# NixiTubeClock.net
KiCad netlist of a schematic drawn in EAGLE
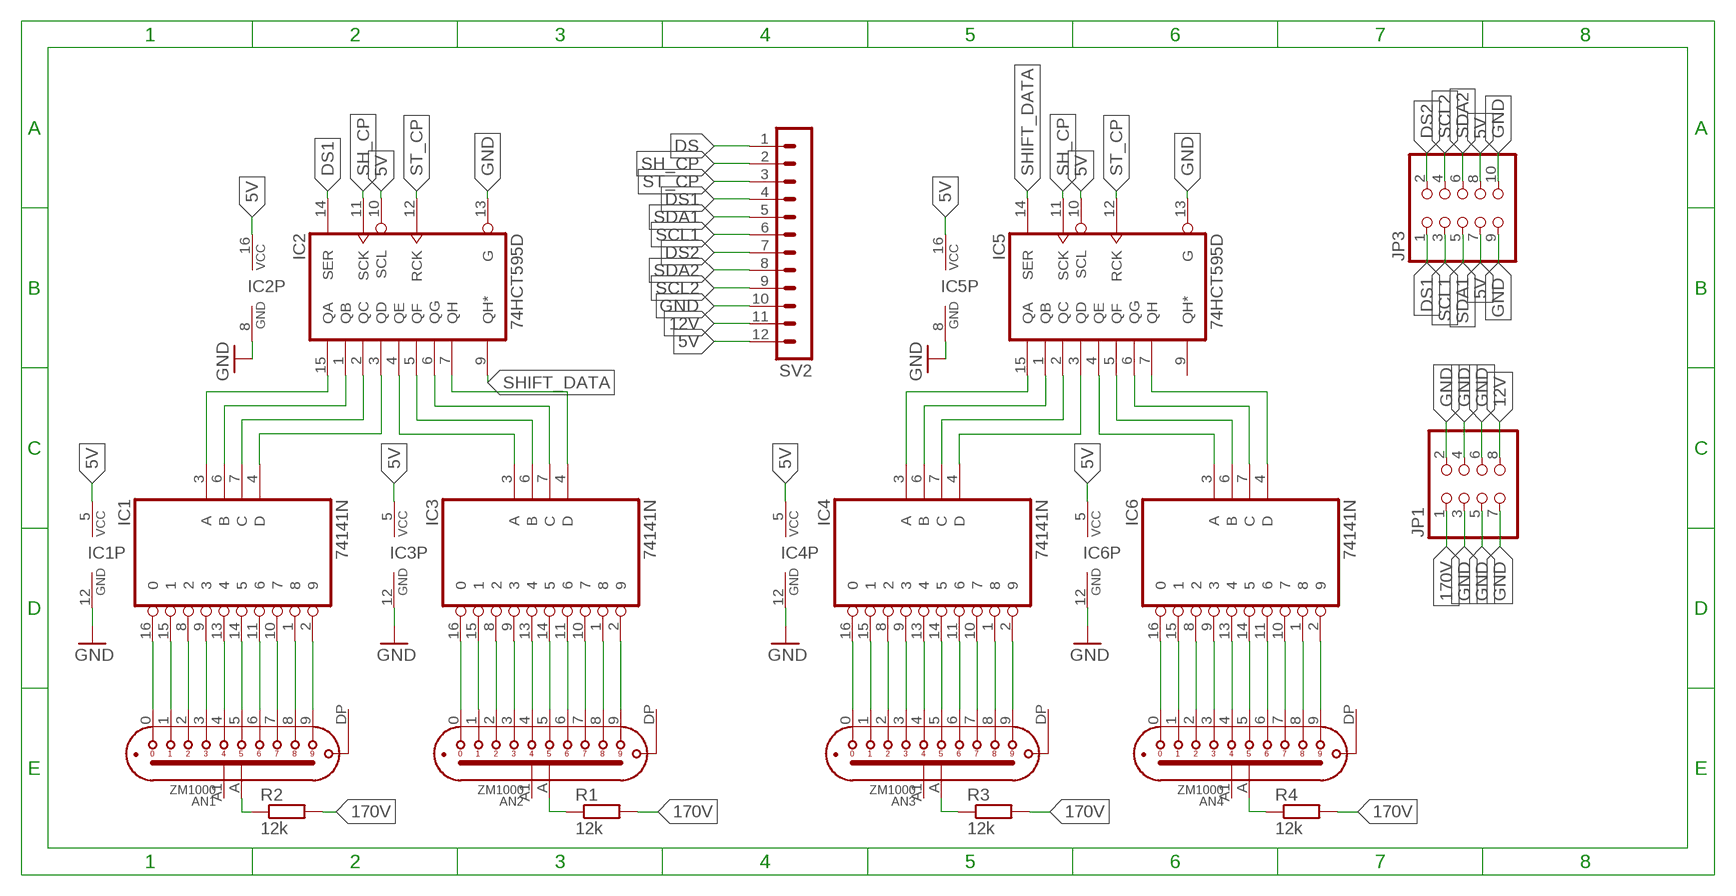
[diagram p0: schematic, sheet 1]
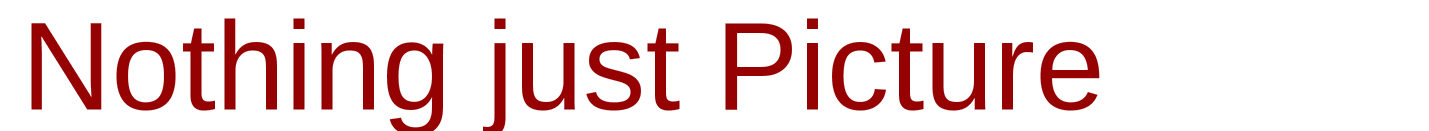
[diagram p1: schematic, sheet 2]

(export (version "E")
  (design (tool "Eeschema 10.0.6"))
  (components
    (comp (ref "AN1")
      (value "ZM1000")
      (footprint "eagle-import:ZM1000")
      (libsource (lib "eagle-import") (part "ZM1000"))
    )
    (comp (ref "AN2")
      (value "ZM1000")
      (footprint "eagle-import:ZM1000")
      (libsource (lib "eagle-import") (part "ZM1000"))
    )
    (comp (ref "AN3")
      (value "ZM1000")
      (footprint "eagle-import:ZM1000")
      (libsource (lib "eagle-import") (part "ZM1000"))
    )
    (comp (ref "AN4")
      (value "ZM1000")
      (footprint "eagle-import:ZM1000")
      (libsource (lib "eagle-import") (part "ZM1000"))
    )
    (comp (ref "IC1")
      (value "74141N")
      (footprint "eagle-import:DIL16")
      (libsource (lib "eagle-import") (part "74141N"))
    )
    (comp (ref "IC2")
      (value "74HCT595D")
      (footprint "eagle-import:SO16")
      (libsource (lib "eagle-import") (part "74595DHCT"))
    )
    (comp (ref "IC3")
      (value "74141N")
      (footprint "eagle-import:DIL16")
      (libsource (lib "eagle-import") (part "74141N"))
    )
    (comp (ref "IC4")
      (value "74141N")
      (footprint "eagle-import:DIL16")
      (libsource (lib "eagle-import") (part "74141N"))
    )
    (comp (ref "IC5")
      (value "74HCT595D")
      (footprint "eagle-import:SO16")
      (libsource (lib "eagle-import") (part "74595DHCT"))
    )
    (comp (ref "IC6")
      (value "74141N")
      (footprint "eagle-import:DIL16")
      (libsource (lib "eagle-import") (part "74141N"))
    )
    (comp (ref "JP1")
      (value "PINHD-2X4/90")
      (footprint "eagle-import:2X04_90")
      (libsource (lib "eagle-import") (part "PINHD-2X4/90"))
    )
    (comp (ref "JP3")
      (value "PINHD-2X5/90")
      (footprint "eagle-import:2X05_90")
      (libsource (lib "eagle-import") (part "PINHD-2X5/90"))
    )
    (comp (ref "R1")
      (value "12k")
      (footprint "eagle-import:R1206")
      (libsource (lib "eagle-import") (part "R-EU_1206R1206"))
    )
    (comp (ref "R2")
      (value "12k")
      (footprint "eagle-import:R1206")
      (libsource (lib "eagle-import") (part "R-EU_1206R1206"))
    )
    (comp (ref "R3")
      (value "12k")
      (footprint "eagle-import:R1206")
      (libsource (lib "eagle-import") (part "R-EU_1206R1206"))
    )
    (comp (ref "R4")
      (value "12k")
      (footprint "eagle-import:R1206")
      (libsource (lib "eagle-import") (part "R-EU_1206R1206"))
    )
    (comp (ref "SV2")
      (value "MA12-1")
      (footprint "eagle-import:MA12-1")
      (libsource (lib "eagle-import") (part "MA12-1"))
    )
  )
  (nets
    (net (code "1") (name "5V") (class "Default")
      (node (ref "IC1") (pin "5") (pinfunction "VCC_5") (pintype "power_in"))
      (node (ref "IC2") (pin "10") (pinfunction "SCL_10") (pintype "input"))
      (node (ref "IC2") (pin "16") (pinfunction "VCC_16") (pintype "power_in"))
      (node (ref "IC3") (pin "5") (pinfunction "VCC_5") (pintype "power_in"))
      (node (ref "IC4") (pin "5") (pinfunction "VCC_5") (pintype "power_in"))
      (node (ref "IC5") (pin "10") (pinfunction "SCL_10") (pintype "input"))
      (node (ref "IC5") (pin "16") (pinfunction "VCC_16") (pintype "power_in"))
      (node (ref "IC6") (pin "5") (pinfunction "VCC_5") (pintype "power_in"))
      (node (ref "JP3") (pin "7") (pinfunction "7_7") (pintype "passive"))
      (node (ref "JP3") (pin "8") (pinfunction "8_8") (pintype "passive"))
      (node (ref "SV2") (pin "12") (pinfunction "12_12") (pintype "passive"))
    )
    (net (code "2") (name "12V") (class "Default")
      (node (ref "JP1") (pin "8") (pinfunction "8_8") (pintype "passive"))
      (node (ref "SV2") (pin "11") (pinfunction "11_11") (pintype "passive"))
    )
    (net (code "3") (name "170V") (class "Default")
      (node (ref "JP1") (pin "1") (pinfunction "1_1") (pintype "passive"))
      (node (ref "R1") (pin "2") (pinfunction "2_2") (pintype "passive"))
      (node (ref "R2") (pin "2") (pinfunction "2_2") (pintype "passive"))
      (node (ref "R3") (pin "2") (pinfunction "2_2") (pintype "passive"))
      (node (ref "R4") (pin "2") (pinfunction "2_2") (pintype "passive"))
    )
    (net (code "4") (name "DS") (class "Default")
      (node (ref "SV2") (pin "1") (pinfunction "1_1") (pintype "passive"))
    )
    (net (code "5") (name "DS1") (class "Default")
      (node (ref "IC2") (pin "14") (pinfunction "SER_14") (pintype "input"))
      (node (ref "JP3") (pin "1") (pinfunction "1_1") (pintype "passive"))
      (node (ref "SV2") (pin "4") (pinfunction "4_4") (pintype "passive"))
    )
    (net (code "6") (name "DS2") (class "Default")
      (node (ref "JP3") (pin "2") (pinfunction "2_2") (pintype "passive"))
      (node (ref "SV2") (pin "7") (pinfunction "7_7") (pintype "passive"))
    )
    (net (code "7") (name "GND") (class "Default")
      (node (ref "IC1") (pin "12") (pinfunction "GND_12") (pintype "power_in"))
      (node (ref "IC2") (pin "13") (pinfunction "G_13") (pintype "input"))
      (node (ref "IC2") (pin "8") (pinfunction "GND_8") (pintype "power_in"))
      (node (ref "IC3") (pin "12") (pinfunction "GND_12") (pintype "power_in"))
      (node (ref "IC4") (pin "12") (pinfunction "GND_12") (pintype "power_in"))
      (node (ref "IC5") (pin "13") (pinfunction "G_13") (pintype "input"))
      (node (ref "IC5") (pin "8") (pinfunction "GND_8") (pintype "power_in"))
      (node (ref "IC6") (pin "12") (pinfunction "GND_12") (pintype "power_in"))
      (node (ref "JP1") (pin "2") (pinfunction "2_2") (pintype "passive"))
      (node (ref "JP1") (pin "3") (pinfunction "3_3") (pintype "passive"))
      (node (ref "JP1") (pin "4") (pinfunction "4_4") (pintype "passive"))
      (node (ref "JP1") (pin "5") (pinfunction "5_5") (pintype "passive"))
      (node (ref "JP1") (pin "6") (pinfunction "6_6") (pintype "passive"))
      (node (ref "JP1") (pin "7") (pinfunction "7_7") (pintype "passive"))
      (node (ref "JP3") (pin "10") (pinfunction "10_10") (pintype "passive"))
      (node (ref "JP3") (pin "9") (pinfunction "9_9") (pintype "passive"))
      (node (ref "SV2") (pin "10") (pinfunction "10_10") (pintype "passive"))
    )
    (net (code "8") (name "Net-(AN1-A1)") (class "Default")
      (node (ref "AN1") (pin "A") (pinfunction "A1_A") (pintype "passive"))
      (node (ref "R2") (pin "1") (pinfunction "1_1") (pintype "passive"))
    )
    (net (code "9") (name "Net-(AN2-A1)") (class "Default")
      (node (ref "AN2") (pin "A") (pinfunction "A1_A") (pintype "passive"))
      (node (ref "R1") (pin "1") (pinfunction "1_1") (pintype "passive"))
    )
    (net (code "10") (name "Net-(AN3-A1)") (class "Default")
      (node (ref "AN3") (pin "A") (pinfunction "A1_A") (pintype "passive"))
      (node (ref "R3") (pin "1") (pinfunction "1_1") (pintype "passive"))
    )
    (net (code "11") (name "Net-(AN4-A1)") (class "Default")
      (node (ref "AN4") (pin "A") (pinfunction "A1_A") (pintype "passive"))
      (node (ref "R4") (pin "1") (pinfunction "1_1") (pintype "passive"))
    )
    (net (code "12") (name "Net-(IC1A-0)") (class "Default")
      (node (ref "AN1") (pin "0") (pinfunction "0_0") (pintype "passive"))
      (node (ref "IC1") (pin "16") (pinfunction "0_16") (pintype "open_collector"))
    )
    (net (code "13") (name "Net-(IC1A-1)") (class "Default")
      (node (ref "AN1") (pin "1") (pinfunction "1_1") (pintype "passive"))
      (node (ref "IC1") (pin "15") (pinfunction "1_15") (pintype "open_collector"))
    )
    (net (code "14") (name "Net-(IC1A-2)") (class "Default")
      (node (ref "AN1") (pin "2") (pinfunction "2_2") (pintype "passive"))
      (node (ref "IC1") (pin "8") (pinfunction "2_8") (pintype "open_collector"))
    )
    (net (code "15") (name "Net-(IC1A-3)") (class "Default")
      (node (ref "AN1") (pin "3") (pinfunction "3_3") (pintype "passive"))
      (node (ref "IC1") (pin "9") (pinfunction "3_9") (pintype "open_collector"))
    )
    (net (code "16") (name "Net-(IC1A-4)") (class "Default")
      (node (ref "AN1") (pin "4") (pinfunction "4_4") (pintype "passive"))
      (node (ref "IC1") (pin "13") (pinfunction "4_13") (pintype "open_collector"))
    )
    (net (code "17") (name "Net-(IC1A-5)") (class "Default")
      (node (ref "AN1") (pin "5") (pinfunction "5_5") (pintype "passive"))
      (node (ref "IC1") (pin "14") (pinfunction "5_14") (pintype "open_collector"))
    )
    (net (code "18") (name "Net-(IC1A-6)") (class "Default")
      (node (ref "AN1") (pin "6") (pinfunction "6_6") (pintype "passive"))
      (node (ref "IC1") (pin "11") (pinfunction "6_11") (pintype "open_collector"))
    )
    (net (code "19") (name "Net-(IC1A-7)") (class "Default")
      (node (ref "AN1") (pin "7") (pinfunction "7_7") (pintype "passive"))
      (node (ref "IC1") (pin "10") (pinfunction "7_10") (pintype "open_collector"))
    )
    (net (code "20") (name "Net-(IC1A-8)") (class "Default")
      (node (ref "AN1") (pin "8") (pinfunction "8_8") (pintype "passive"))
      (node (ref "IC1") (pin "1") (pinfunction "8_1") (pintype "open_collector"))
    )
    (net (code "21") (name "Net-(IC1A-9)") (class "Default")
      (node (ref "AN1") (pin "9") (pinfunction "9_9") (pintype "passive"))
      (node (ref "IC1") (pin "2") (pinfunction "9_2") (pintype "open_collector"))
    )
    (net (code "22") (name "Net-(IC1A-A)") (class "Default")
      (node (ref "IC1") (pin "3") (pinfunction "A_3") (pintype "input"))
      (node (ref "IC2") (pin "15") (pinfunction "QA_15") (pintype "tri_state"))
    )
    (net (code "23") (name "Net-(IC1A-B)") (class "Default")
      (node (ref "IC1") (pin "6") (pinfunction "B_6") (pintype "input"))
      (node (ref "IC2") (pin "1") (pinfunction "QB_1") (pintype "tri_state"))
    )
    (net (code "24") (name "Net-(IC1A-C)") (class "Default")
      (node (ref "IC1") (pin "7") (pinfunction "C_7") (pintype "input"))
      (node (ref "IC2") (pin "2") (pinfunction "QC_2") (pintype "tri_state"))
    )
    (net (code "25") (name "Net-(IC1A-D)") (class "Default")
      (node (ref "IC1") (pin "4") (pinfunction "D_4") (pintype "input"))
      (node (ref "IC2") (pin "3") (pinfunction "QD_3") (pintype "tri_state"))
    )
    (net (code "26") (name "Net-(IC2A-QE)") (class "Default")
      (node (ref "IC2") (pin "4") (pinfunction "QE_4") (pintype "tri_state"))
      (node (ref "IC3") (pin "3") (pinfunction "A_3") (pintype "input"))
    )
    (net (code "27") (name "Net-(IC2A-QF)") (class "Default")
      (node (ref "IC2") (pin "5") (pinfunction "QF_5") (pintype "tri_state"))
      (node (ref "IC3") (pin "6") (pinfunction "B_6") (pintype "input"))
    )
    (net (code "28") (name "Net-(IC2A-QG)") (class "Default")
      (node (ref "IC2") (pin "6") (pinfunction "QG_6") (pintype "tri_state"))
      (node (ref "IC3") (pin "7") (pinfunction "C_7") (pintype "input"))
    )
    (net (code "29") (name "Net-(IC2A-QH)") (class "Default")
      (node (ref "IC2") (pin "7") (pinfunction "QH_7") (pintype "tri_state"))
      (node (ref "IC3") (pin "4") (pinfunction "D_4") (pintype "input"))
    )
    (net (code "30") (name "Net-(IC3A-0)") (class "Default")
      (node (ref "AN2") (pin "0") (pinfunction "0_0") (pintype "passive"))
      (node (ref "IC3") (pin "16") (pinfunction "0_16") (pintype "open_collector"))
    )
    (net (code "31") (name "Net-(IC3A-1)") (class "Default")
      (node (ref "AN2") (pin "1") (pinfunction "1_1") (pintype "passive"))
      (node (ref "IC3") (pin "15") (pinfunction "1_15") (pintype "open_collector"))
    )
    (net (code "32") (name "Net-(IC3A-2)") (class "Default")
      (node (ref "AN2") (pin "2") (pinfunction "2_2") (pintype "passive"))
      (node (ref "IC3") (pin "8") (pinfunction "2_8") (pintype "open_collector"))
    )
    (net (code "33") (name "Net-(IC3A-3)") (class "Default")
      (node (ref "AN2") (pin "3") (pinfunction "3_3") (pintype "passive"))
      (node (ref "IC3") (pin "9") (pinfunction "3_9") (pintype "open_collector"))
    )
    (net (code "34") (name "Net-(IC3A-4)") (class "Default")
      (node (ref "AN2") (pin "4") (pinfunction "4_4") (pintype "passive"))
      (node (ref "IC3") (pin "13") (pinfunction "4_13") (pintype "open_collector"))
    )
    (net (code "35") (name "Net-(IC3A-5)") (class "Default")
      (node (ref "AN2") (pin "5") (pinfunction "5_5") (pintype "passive"))
      (node (ref "IC3") (pin "14") (pinfunction "5_14") (pintype "open_collector"))
    )
    (net (code "36") (name "Net-(IC3A-6)") (class "Default")
      (node (ref "AN2") (pin "6") (pinfunction "6_6") (pintype "passive"))
      (node (ref "IC3") (pin "11") (pinfunction "6_11") (pintype "open_collector"))
    )
    (net (code "37") (name "Net-(IC3A-7)") (class "Default")
      (node (ref "AN2") (pin "7") (pinfunction "7_7") (pintype "passive"))
      (node (ref "IC3") (pin "10") (pinfunction "7_10") (pintype "open_collector"))
    )
    (net (code "38") (name "Net-(IC3A-8)") (class "Default")
      (node (ref "AN2") (pin "8") (pinfunction "8_8") (pintype "passive"))
      (node (ref "IC3") (pin "1") (pinfunction "8_1") (pintype "open_collector"))
    )
    (net (code "39") (name "Net-(IC3A-9)") (class "Default")
      (node (ref "AN2") (pin "9") (pinfunction "9_9") (pintype "passive"))
      (node (ref "IC3") (pin "2") (pinfunction "9_2") (pintype "open_collector"))
    )
    (net (code "40") (name "Net-(IC4A-0)") (class "Default")
      (node (ref "AN3") (pin "0") (pinfunction "0_0") (pintype "passive"))
      (node (ref "IC4") (pin "16") (pinfunction "0_16") (pintype "open_collector"))
    )
    (net (code "41") (name "Net-(IC4A-1)") (class "Default")
      (node (ref "AN3") (pin "1") (pinfunction "1_1") (pintype "passive"))
      (node (ref "IC4") (pin "15") (pinfunction "1_15") (pintype "open_collector"))
    )
    (net (code "42") (name "Net-(IC4A-2)") (class "Default")
      (node (ref "AN3") (pin "2") (pinfunction "2_2") (pintype "passive"))
      (node (ref "IC4") (pin "8") (pinfunction "2_8") (pintype "open_collector"))
    )
    (net (code "43") (name "Net-(IC4A-3)") (class "Default")
      (node (ref "AN3") (pin "3") (pinfunction "3_3") (pintype "passive"))
      (node (ref "IC4") (pin "9") (pinfunction "3_9") (pintype "open_collector"))
    )
    (net (code "44") (name "Net-(IC4A-4)") (class "Default")
      (node (ref "AN3") (pin "4") (pinfunction "4_4") (pintype "passive"))
      (node (ref "IC4") (pin "13") (pinfunction "4_13") (pintype "open_collector"))
    )
    (net (code "45") (name "Net-(IC4A-5)") (class "Default")
      (node (ref "AN3") (pin "5") (pinfunction "5_5") (pintype "passive"))
      (node (ref "IC4") (pin "14") (pinfunction "5_14") (pintype "open_collector"))
    )
    (net (code "46") (name "Net-(IC4A-6)") (class "Default")
      (node (ref "AN3") (pin "6") (pinfunction "6_6") (pintype "passive"))
      (node (ref "IC4") (pin "11") (pinfunction "6_11") (pintype "open_collector"))
    )
    (net (code "47") (name "Net-(IC4A-7)") (class "Default")
      (node (ref "AN3") (pin "7") (pinfunction "7_7") (pintype "passive"))
      (node (ref "IC4") (pin "10") (pinfunction "7_10") (pintype "open_collector"))
    )
    (net (code "48") (name "Net-(IC4A-8)") (class "Default")
      (node (ref "AN3") (pin "8") (pinfunction "8_8") (pintype "passive"))
      (node (ref "IC4") (pin "1") (pinfunction "8_1") (pintype "open_collector"))
    )
    (net (code "49") (name "Net-(IC4A-9)") (class "Default")
      (node (ref "AN3") (pin "9") (pinfunction "9_9") (pintype "passive"))
      (node (ref "IC4") (pin "2") (pinfunction "9_2") (pintype "open_collector"))
    )
    (net (code "50") (name "Net-(IC4A-A)") (class "Default")
      (node (ref "IC4") (pin "3") (pinfunction "A_3") (pintype "input"))
      (node (ref "IC5") (pin "15") (pinfunction "QA_15") (pintype "tri_state"))
    )
    (net (code "51") (name "Net-(IC4A-B)") (class "Default")
      (node (ref "IC4") (pin "6") (pinfunction "B_6") (pintype "input"))
      (node (ref "IC5") (pin "1") (pinfunction "QB_1") (pintype "tri_state"))
    )
    (net (code "52") (name "Net-(IC4A-C)") (class "Default")
      (node (ref "IC4") (pin "7") (pinfunction "C_7") (pintype "input"))
      (node (ref "IC5") (pin "2") (pinfunction "QC_2") (pintype "tri_state"))
    )
    (net (code "53") (name "Net-(IC4A-D)") (class "Default")
      (node (ref "IC4") (pin "4") (pinfunction "D_4") (pintype "input"))
      (node (ref "IC5") (pin "3") (pinfunction "QD_3") (pintype "tri_state"))
    )
    (net (code "54") (name "Net-(IC5A-QE)") (class "Default")
      (node (ref "IC5") (pin "4") (pinfunction "QE_4") (pintype "tri_state"))
      (node (ref "IC6") (pin "3") (pinfunction "A_3") (pintype "input"))
    )
    (net (code "55") (name "Net-(IC5A-QF)") (class "Default")
      (node (ref "IC5") (pin "5") (pinfunction "QF_5") (pintype "tri_state"))
      (node (ref "IC6") (pin "6") (pinfunction "B_6") (pintype "input"))
    )
    (net (code "56") (name "Net-(IC5A-QG)") (class "Default")
      (node (ref "IC5") (pin "6") (pinfunction "QG_6") (pintype "tri_state"))
      (node (ref "IC6") (pin "7") (pinfunction "C_7") (pintype "input"))
    )
    (net (code "57") (name "Net-(IC5A-QH)") (class "Default")
      (node (ref "IC5") (pin "7") (pinfunction "QH_7") (pintype "tri_state"))
      (node (ref "IC6") (pin "4") (pinfunction "D_4") (pintype "input"))
    )
    (net (code "58") (name "Net-(IC6A-0)") (class "Default")
      (node (ref "AN4") (pin "0") (pinfunction "0_0") (pintype "passive"))
      (node (ref "IC6") (pin "16") (pinfunction "0_16") (pintype "open_collector"))
    )
    (net (code "59") (name "Net-(IC6A-1)") (class "Default")
      (node (ref "AN4") (pin "1") (pinfunction "1_1") (pintype "passive"))
      (node (ref "IC6") (pin "15") (pinfunction "1_15") (pintype "open_collector"))
    )
    (net (code "60") (name "Net-(IC6A-2)") (class "Default")
      (node (ref "AN4") (pin "2") (pinfunction "2_2") (pintype "passive"))
      (node (ref "IC6") (pin "8") (pinfunction "2_8") (pintype "open_collector"))
    )
    (net (code "61") (name "Net-(IC6A-3)") (class "Default")
      (node (ref "AN4") (pin "3") (pinfunction "3_3") (pintype "passive"))
      (node (ref "IC6") (pin "9") (pinfunction "3_9") (pintype "open_collector"))
    )
    (net (code "62") (name "Net-(IC6A-4)") (class "Default")
      (node (ref "AN4") (pin "4") (pinfunction "4_4") (pintype "passive"))
      (node (ref "IC6") (pin "13") (pinfunction "4_13") (pintype "open_collector"))
    )
    (net (code "63") (name "Net-(IC6A-5)") (class "Default")
      (node (ref "AN4") (pin "5") (pinfunction "5_5") (pintype "passive"))
      (node (ref "IC6") (pin "14") (pinfunction "5_14") (pintype "open_collector"))
    )
    (net (code "64") (name "Net-(IC6A-6)") (class "Default")
      (node (ref "AN4") (pin "6") (pinfunction "6_6") (pintype "passive"))
      (node (ref "IC6") (pin "11") (pinfunction "6_11") (pintype "open_collector"))
    )
    (net (code "65") (name "Net-(IC6A-7)") (class "Default")
      (node (ref "AN4") (pin "7") (pinfunction "7_7") (pintype "passive"))
      (node (ref "IC6") (pin "10") (pinfunction "7_10") (pintype "open_collector"))
    )
    (net (code "66") (name "Net-(IC6A-8)") (class "Default")
      (node (ref "AN4") (pin "8") (pinfunction "8_8") (pintype "passive"))
      (node (ref "IC6") (pin "1") (pinfunction "8_1") (pintype "open_collector"))
    )
    (net (code "67") (name "Net-(IC6A-9)") (class "Default")
      (node (ref "AN4") (pin "9") (pinfunction "9_9") (pintype "passive"))
      (node (ref "IC6") (pin "2") (pinfunction "9_2") (pintype "open_collector"))
    )
    (net (code "68") (name "SCL1") (class "Default")
      (node (ref "JP3") (pin "3") (pinfunction "3_3") (pintype "passive"))
      (node (ref "SV2") (pin "6") (pinfunction "6_6") (pintype "passive"))
    )
    (net (code "69") (name "SCL2") (class "Default")
      (node (ref "JP3") (pin "4") (pinfunction "4_4") (pintype "passive"))
      (node (ref "SV2") (pin "9") (pinfunction "9_9") (pintype "passive"))
    )
    (net (code "70") (name "SDA1") (class "Default")
      (node (ref "JP3") (pin "5") (pinfunction "5_5") (pintype "passive"))
      (node (ref "SV2") (pin "5") (pinfunction "5_5") (pintype "passive"))
    )
    (net (code "71") (name "SDA2") (class "Default")
      (node (ref "JP3") (pin "6") (pinfunction "6_6") (pintype "passive"))
      (node (ref "SV2") (pin "8") (pinfunction "8_8") (pintype "passive"))
    )
    (net (code "72") (name "SHIFT_DATA") (class "Default")
      (node (ref "IC2") (pin "9") (pinfunction "QH*_9") (pintype "tri_state"))
      (node (ref "IC5") (pin "14") (pinfunction "SER_14") (pintype "input"))
    )
    (net (code "73") (name "SH_CP") (class "Default")
      (node (ref "IC2") (pin "11") (pinfunction "SCK_11") (pintype "input"))
      (node (ref "IC5") (pin "11") (pinfunction "SCK_11") (pintype "input"))
      (node (ref "SV2") (pin "2") (pinfunction "2_2") (pintype "passive"))
    )
    (net (code "74") (name "ST_CP") (class "Default")
      (node (ref "IC2") (pin "12") (pinfunction "RCK_12") (pintype "input"))
      (node (ref "IC5") (pin "12") (pinfunction "RCK_12") (pintype "input"))
      (node (ref "SV2") (pin "3") (pinfunction "3_3") (pintype "passive"))
    )
    (net (code "75") (name "unconnected-(AN1-A2-PadA1)") (class "Default")
      (node (ref "AN1") (pin "A1") (pinfunction "A2_A1") (pintype "passive"))
    )
    (net (code "76") (name "unconnected-(AN1-DPL-PadDP)") (class "Default")
      (node (ref "AN1") (pin "DP") (pinfunction "DPL_DP") (pintype "passive"))
    )
    (net (code "77") (name "unconnected-(AN2-A2-PadA1)") (class "Default")
      (node (ref "AN2") (pin "A1") (pinfunction "A2_A1") (pintype "passive"))
    )
    (net (code "78") (name "unconnected-(AN2-DPL-PadDP)") (class "Default")
      (node (ref "AN2") (pin "DP") (pinfunction "DPL_DP") (pintype "passive"))
    )
    (net (code "79") (name "unconnected-(AN3-A2-PadA1)") (class "Default")
      (node (ref "AN3") (pin "A1") (pinfunction "A2_A1") (pintype "passive"))
    )
    (net (code "80") (name "unconnected-(AN3-DPL-PadDP)") (class "Default")
      (node (ref "AN3") (pin "DP") (pinfunction "DPL_DP") (pintype "passive"))
    )
    (net (code "81") (name "unconnected-(AN4-A2-PadA1)") (class "Default")
      (node (ref "AN4") (pin "A1") (pinfunction "A2_A1") (pintype "passive"))
    )
    (net (code "82") (name "unconnected-(AN4-DPL-PadDP)") (class "Default")
      (node (ref "AN4") (pin "DP") (pinfunction "DPL_DP") (pintype "passive"))
    )
    (net (code "83") (name "unconnected-(IC5A-QH*-Pad9)") (class "Default")
      (node (ref "IC5") (pin "9") (pinfunction "QH*_9") (pintype "tri_state"))
    )
  )
)
